# Arduino_R3_Half.net
KiCad netlist of a schematic drawn in EAGLE
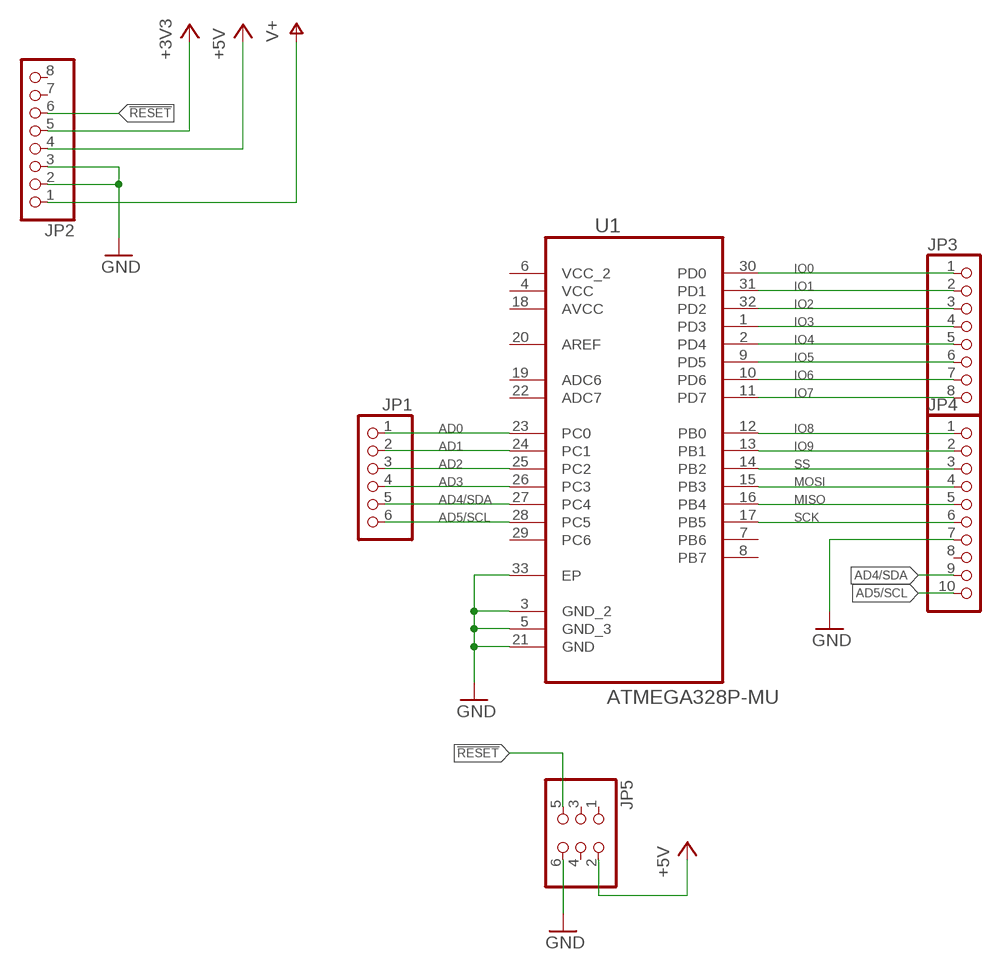
[diagram p0: schematic, sheet 1]

(export (version "E")
  (design (tool "Eeschema 10.0.6"))
  (components
    (comp (ref "JP1")
      (value "PINHD-1X6")
      (footprint "eagle-import:1X06")
      (libsource (lib "eagle-import") (part "PINHD-1X6"))
    )
    (comp (ref "JP2")
      (value "PINHD-1X8")
      (footprint "eagle-import:1X08")
      (libsource (lib "eagle-import") (part "PINHD-1X8"))
    )
    (comp (ref "JP3")
      (value "PINHD-1X8")
      (footprint "eagle-import:1X08")
      (libsource (lib "eagle-import") (part "PINHD-1X8"))
    )
    (comp (ref "JP4")
      (value "PINHD-1X10")
      (footprint "eagle-import:1X10")
      (libsource (lib "eagle-import") (part "PINHD-1X10"))
    )
    (comp (ref "JP5")
      (value "PINHD-2X3")
      (footprint "eagle-import:2X03")
      (libsource (lib "eagle-import") (part "PINHD-2X3"))
    )
    (comp (ref "U1")
      (value "ATMEGA328P-MU")
      (footprint "eagle-import:QFN50P500X500X100-33N")
      (libsource (lib "eagle-import") (part "ATMEGA328P-MU"))
    )
  )
  (nets
    (net (code "1") (name "+3V3") (class "Default")
      (node (ref "JP2") (pin "5") (pinfunction "5_5") (pintype "passive"))
    )
    (net (code "2") (name "+5V") (class "Default")
      (node (ref "JP2") (pin "4") (pinfunction "4_4") (pintype "passive"))
      (node (ref "JP5") (pin "2") (pinfunction "2_2") (pintype "passive"))
    )
    (net (code "3") (name "/AD0") (class "Default")
      (node (ref "JP1") (pin "1") (pinfunction "1_1") (pintype "passive"))
      (node (ref "U1") (pin "23") (pinfunction "PC0_23") (pintype "bidirectional"))
    )
    (net (code "4") (name "/AD1") (class "Default")
      (node (ref "JP1") (pin "2") (pinfunction "2_2") (pintype "passive"))
      (node (ref "U1") (pin "24") (pinfunction "PC1_24") (pintype "bidirectional"))
    )
    (net (code "5") (name "/AD2") (class "Default")
      (node (ref "JP1") (pin "3") (pinfunction "3_3") (pintype "passive"))
      (node (ref "U1") (pin "25") (pinfunction "PC2_25") (pintype "bidirectional"))
    )
    (net (code "6") (name "/AD3") (class "Default")
      (node (ref "JP1") (pin "4") (pinfunction "4_4") (pintype "passive"))
      (node (ref "U1") (pin "26") (pinfunction "PC3_26") (pintype "bidirectional"))
    )
    (net (code "7") (name "/AVCC") (class "Default")
      (node (ref "U1") (pin "18") (pinfunction "AVCC_18") (pintype "power_in"))
    )
    (net (code "8") (name "/IO0") (class "Default")
      (node (ref "JP3") (pin "1") (pinfunction "1_1") (pintype "passive"))
      (node (ref "U1") (pin "30") (pinfunction "PD0_30") (pintype "bidirectional"))
    )
    (net (code "9") (name "/IO1") (class "Default")
      (node (ref "JP3") (pin "2") (pinfunction "2_2") (pintype "passive"))
      (node (ref "U1") (pin "31") (pinfunction "PD1_31") (pintype "bidirectional"))
    )
    (net (code "10") (name "/IO2") (class "Default")
      (node (ref "JP3") (pin "3") (pinfunction "3_3") (pintype "passive"))
      (node (ref "U1") (pin "32") (pinfunction "PD2_32") (pintype "bidirectional"))
    )
    (net (code "11") (name "/IO3") (class "Default")
      (node (ref "JP3") (pin "4") (pinfunction "4_4") (pintype "passive"))
      (node (ref "U1") (pin "1") (pinfunction "PD3_1") (pintype "bidirectional"))
    )
    (net (code "12") (name "/IO4") (class "Default")
      (node (ref "JP3") (pin "5") (pinfunction "5_5") (pintype "passive"))
      (node (ref "U1") (pin "2") (pinfunction "PD4_2") (pintype "bidirectional"))
    )
    (net (code "13") (name "/IO5") (class "Default")
      (node (ref "JP3") (pin "6") (pinfunction "6_6") (pintype "passive"))
      (node (ref "U1") (pin "9") (pinfunction "PD5_9") (pintype "bidirectional"))
    )
    (net (code "14") (name "/IO6") (class "Default")
      (node (ref "JP3") (pin "7") (pinfunction "7_7") (pintype "passive"))
      (node (ref "U1") (pin "10") (pinfunction "PD6_10") (pintype "bidirectional"))
    )
    (net (code "15") (name "/IO7") (class "Default")
      (node (ref "JP3") (pin "8") (pinfunction "8_8") (pintype "passive"))
      (node (ref "U1") (pin "11") (pinfunction "PD7_11") (pintype "bidirectional"))
    )
    (net (code "16") (name "/IO8") (class "Default")
      (node (ref "JP4") (pin "1") (pinfunction "1_1") (pintype "passive"))
      (node (ref "U1") (pin "12") (pinfunction "PB0_12") (pintype "bidirectional"))
    )
    (net (code "17") (name "/IO9") (class "Default")
      (node (ref "JP4") (pin "2") (pinfunction "2_2") (pintype "passive"))
      (node (ref "U1") (pin "13") (pinfunction "PB1_13") (pintype "bidirectional"))
    )
    (net (code "18") (name "/MISO") (class "Default")
      (node (ref "JP4") (pin "5") (pinfunction "5_5") (pintype "passive"))
      (node (ref "U1") (pin "16") (pinfunction "PB4_16") (pintype "bidirectional"))
    )
    (net (code "19") (name "/MOSI") (class "Default")
      (node (ref "JP4") (pin "4") (pinfunction "4_4") (pintype "passive"))
      (node (ref "U1") (pin "15") (pinfunction "PB3_15") (pintype "bidirectional"))
    )
    (net (code "20") (name "/SCK") (class "Default")
      (node (ref "JP4") (pin "6") (pinfunction "6_6") (pintype "passive"))
      (node (ref "U1") (pin "17") (pinfunction "PB5_17") (pintype "bidirectional"))
    )
    (net (code "21") (name "/SS") (class "Default")
      (node (ref "JP4") (pin "3") (pinfunction "3_3") (pintype "passive"))
      (node (ref "U1") (pin "14") (pinfunction "PB2_14") (pintype "bidirectional"))
    )
    (net (code "22") (name "/VCC") (class "Default")
      (node (ref "U1") (pin "4") (pinfunction "VCC_4") (pintype "power_in"))
    )
    (net (code "23") (name "/VCC_2") (class "Default")
      (node (ref "U1") (pin "6") (pinfunction "VCC_2_6") (pintype "power_in"))
    )
    (net (code "24") (name "/~{RESET}") (class "Default")
      (node (ref "JP2") (pin "6") (pinfunction "6_6") (pintype "passive"))
      (node (ref "JP5") (pin "5") (pinfunction "5_5") (pintype "passive"))
    )
    (net (code "25") (name "AD4{slash}SDA") (class "Default")
      (node (ref "JP1") (pin "5") (pinfunction "5_5") (pintype "passive"))
      (node (ref "JP4") (pin "9") (pinfunction "9_9") (pintype "passive"))
      (node (ref "U1") (pin "27") (pinfunction "PC4_27") (pintype "bidirectional"))
    )
    (net (code "26") (name "AD5{slash}SCL") (class "Default")
      (node (ref "JP1") (pin "6") (pinfunction "6_6") (pintype "passive"))
      (node (ref "JP4") (pin "10") (pinfunction "10_10") (pintype "passive"))
      (node (ref "U1") (pin "28") (pinfunction "PC5_28") (pintype "bidirectional"))
    )
    (net (code "27") (name "GND") (class "Default")
      (node (ref "JP2") (pin "2") (pinfunction "2_2") (pintype "passive"))
      (node (ref "JP2") (pin "3") (pinfunction "3_3") (pintype "passive"))
      (node (ref "JP4") (pin "7") (pinfunction "7_7") (pintype "passive"))
      (node (ref "JP5") (pin "6") (pinfunction "6_6") (pintype "passive"))
      (node (ref "U1") (pin "21") (pinfunction "GND_21") (pintype "passive"))
      (node (ref "U1") (pin "3") (pinfunction "GND_2_3") (pintype "passive"))
      (node (ref "U1") (pin "33") (pinfunction "EP_33") (pintype "passive"))
      (node (ref "U1") (pin "5") (pinfunction "GND_3_5") (pintype "passive"))
    )
    (net (code "28") (name "V+") (class "Default")
      (node (ref "JP2") (pin "1") (pinfunction "1_1") (pintype "passive"))
    )
    (net (code "29") (name "unconnected-(JP2-Pad7)") (class "Default")
      (node (ref "JP2") (pin "7") (pinfunction "7_7") (pintype "passive"))
    )
    (net (code "30") (name "unconnected-(JP2-Pad8)") (class "Default")
      (node (ref "JP2") (pin "8") (pinfunction "8_8") (pintype "passive"))
    )
    (net (code "31") (name "unconnected-(JP4-Pad8)") (class "Default")
      (node (ref "JP4") (pin "8") (pinfunction "8_8") (pintype "passive"))
    )
    (net (code "32") (name "unconnected-(JP5-Pad1)") (class "Default")
      (node (ref "JP5") (pin "1") (pinfunction "1_1") (pintype "passive"))
    )
    (net (code "33") (name "unconnected-(JP5-Pad3)") (class "Default")
      (node (ref "JP5") (pin "3") (pinfunction "3_3") (pintype "passive"))
    )
    (net (code "34") (name "unconnected-(JP5-Pad4)") (class "Default")
      (node (ref "JP5") (pin "4") (pinfunction "4_4") (pintype "passive"))
    )
    (net (code "35") (name "unconnected-(U1-ADC6-Pad19)") (class "Default")
      (node (ref "U1") (pin "19") (pinfunction "ADC6_19") (pintype "input"))
    )
    (net (code "36") (name "unconnected-(U1-ADC7-Pad22)") (class "Default")
      (node (ref "U1") (pin "22") (pinfunction "ADC7_22") (pintype "input"))
    )
    (net (code "37") (name "unconnected-(U1-AREF-Pad20)") (class "Default")
      (node (ref "U1") (pin "20") (pinfunction "AREF_20") (pintype "input"))
    )
    (net (code "38") (name "unconnected-(U1-PB6-Pad7)") (class "Default")
      (node (ref "U1") (pin "7") (pinfunction "PB6_7") (pintype "bidirectional"))
    )
    (net (code "39") (name "unconnected-(U1-PB7-Pad8)") (class "Default")
      (node (ref "U1") (pin "8") (pinfunction "PB7_8") (pintype "bidirectional"))
    )
    (net (code "40") (name "unconnected-(U1-PC6-Pad29)") (class "Default")
      (node (ref "U1") (pin "29") (pinfunction "PC6_29") (pintype "bidirectional"))
    )
  )
)
